# led_driver2.net
KiCad netlist of a schematic drawn in EAGLE
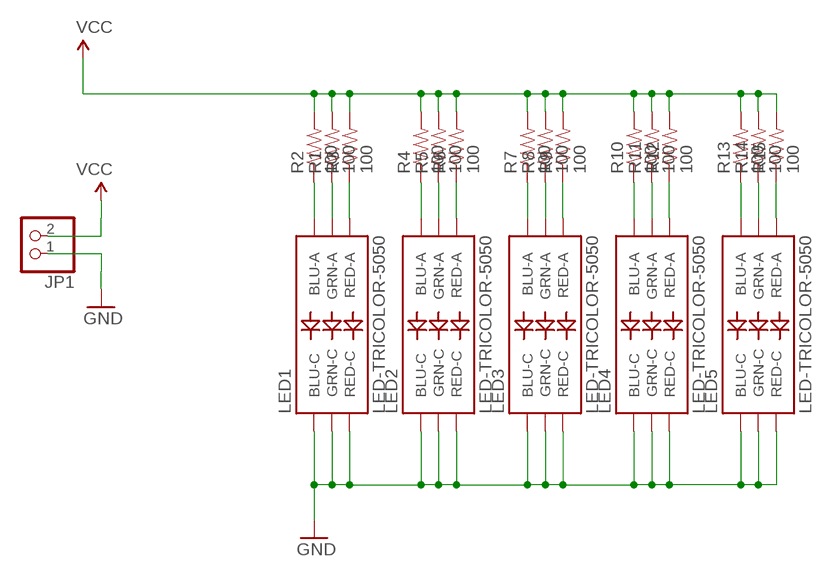
[diagram p0: schematic, sheet 1]

(export (version "E")
  (design (tool "Eeschema 10.0.6"))
  (components
    (comp (ref "JP1")
      (value "PINHD-1X2")
      (footprint "eagle-import:1X02")
      (libsource (lib "eagle-import") (part "PINHD-1X2"))
    )
    (comp (ref "LED1")
      (value "LED-TRICOLOR-5050")
      (footprint "eagle-import:LED-TRICOLOR-5050")
      (libsource (lib "eagle-import") (part "LED-TRICOLOR-5050"))
    )
    (comp (ref "LED2")
      (value "LED-TRICOLOR-5050")
      (footprint "eagle-import:LED-TRICOLOR-5050")
      (libsource (lib "eagle-import") (part "LED-TRICOLOR-5050"))
    )
    (comp (ref "LED3")
      (value "LED-TRICOLOR-5050")
      (footprint "eagle-import:LED-TRICOLOR-5050")
      (libsource (lib "eagle-import") (part "LED-TRICOLOR-5050"))
    )
    (comp (ref "LED4")
      (value "LED-TRICOLOR-5050")
      (footprint "eagle-import:LED-TRICOLOR-5050")
      (libsource (lib "eagle-import") (part "LED-TRICOLOR-5050"))
    )
    (comp (ref "LED5")
      (value "LED-TRICOLOR-5050")
      (footprint "eagle-import:LED-TRICOLOR-5050")
      (libsource (lib "eagle-import") (part "LED-TRICOLOR-5050"))
    )
    (comp (ref "R1")
      (value "100")
      (footprint "eagle-import:0603-RES")
      (libsource (lib "eagle-import") (part "RESISTOR0603-RES"))
    )
    (comp (ref "R2")
      (value "100")
      (footprint "eagle-import:0603-RES")
      (libsource (lib "eagle-import") (part "RESISTOR0603-RES"))
    )
    (comp (ref "R3")
      (value "100")
      (footprint "eagle-import:0603-RES")
      (libsource (lib "eagle-import") (part "RESISTOR0603-RES"))
    )
    (comp (ref "R4")
      (value "100")
      (footprint "eagle-import:0603-RES")
      (libsource (lib "eagle-import") (part "RESISTOR0603-RES"))
    )
    (comp (ref "R5")
      (value "100")
      (footprint "eagle-import:0603-RES")
      (libsource (lib "eagle-import") (part "RESISTOR0603-RES"))
    )
    (comp (ref "R6")
      (value "100")
      (footprint "eagle-import:0603-RES")
      (libsource (lib "eagle-import") (part "RESISTOR0603-RES"))
    )
    (comp (ref "R7")
      (value "100")
      (footprint "eagle-import:0603-RES")
      (libsource (lib "eagle-import") (part "RESISTOR0603-RES"))
    )
    (comp (ref "R8")
      (value "100")
      (footprint "eagle-import:0603-RES")
      (libsource (lib "eagle-import") (part "RESISTOR0603-RES"))
    )
    (comp (ref "R9")
      (value "100")
      (footprint "eagle-import:0603-RES")
      (libsource (lib "eagle-import") (part "RESISTOR0603-RES"))
    )
    (comp (ref "R10")
      (value "100")
      (footprint "eagle-import:0603-RES")
      (libsource (lib "eagle-import") (part "RESISTOR0603-RES"))
    )
    (comp (ref "R11")
      (value "100")
      (footprint "eagle-import:0603-RES")
      (libsource (lib "eagle-import") (part "RESISTOR0603-RES"))
    )
    (comp (ref "R12")
      (value "100")
      (footprint "eagle-import:0603-RES")
      (libsource (lib "eagle-import") (part "RESISTOR0603-RES"))
    )
    (comp (ref "R13")
      (value "100")
      (footprint "eagle-import:0603-RES")
      (libsource (lib "eagle-import") (part "RESISTOR0603-RES"))
    )
    (comp (ref "R14")
      (value "100")
      (footprint "eagle-import:0603-RES")
      (libsource (lib "eagle-import") (part "RESISTOR0603-RES"))
    )
    (comp (ref "R15")
      (value "100")
      (footprint "eagle-import:0603-RES")
      (libsource (lib "eagle-import") (part "RESISTOR0603-RES"))
    )
  )
  (nets
    (net (code "1") (name "GND") (class "Default")
      (node (ref "JP1") (pin "1") (pinfunction "1_1") (pintype "passive"))
      (node (ref "LED1") (pin "4") (pinfunction "BLU-C_4") (pintype "bidirectional"))
      (node (ref "LED1") (pin "5") (pinfunction "RED-C_5") (pintype "bidirectional"))
      (node (ref "LED1") (pin "6") (pinfunction "GRN-C_6") (pintype "bidirectional"))
      (node (ref "LED2") (pin "4") (pinfunction "BLU-C_4") (pintype "bidirectional"))
      (node (ref "LED2") (pin "5") (pinfunction "RED-C_5") (pintype "bidirectional"))
      (node (ref "LED2") (pin "6") (pinfunction "GRN-C_6") (pintype "bidirectional"))
      (node (ref "LED3") (pin "4") (pinfunction "BLU-C_4") (pintype "bidirectional"))
      (node (ref "LED3") (pin "5") (pinfunction "RED-C_5") (pintype "bidirectional"))
      (node (ref "LED3") (pin "6") (pinfunction "GRN-C_6") (pintype "bidirectional"))
      (node (ref "LED4") (pin "4") (pinfunction "BLU-C_4") (pintype "bidirectional"))
      (node (ref "LED4") (pin "5") (pinfunction "RED-C_5") (pintype "bidirectional"))
      (node (ref "LED4") (pin "6") (pinfunction "GRN-C_6") (pintype "bidirectional"))
      (node (ref "LED5") (pin "4") (pinfunction "BLU-C_4") (pintype "bidirectional"))
      (node (ref "LED5") (pin "5") (pinfunction "RED-C_5") (pintype "bidirectional"))
      (node (ref "LED5") (pin "6") (pinfunction "GRN-C_6") (pintype "bidirectional"))
    )
    (net (code "2") (name "Net-(LED1-BLU-A)") (class "Default")
      (node (ref "LED1") (pin "3") (pinfunction "BLU-A_3") (pintype "bidirectional"))
      (node (ref "R2") (pin "1") (pinfunction "1_1") (pintype "passive"))
    )
    (net (code "3") (name "Net-(LED1-GRN-A)") (class "Default")
      (node (ref "LED1") (pin "1") (pinfunction "GRN-A_1") (pintype "bidirectional"))
      (node (ref "R1") (pin "1") (pinfunction "1_1") (pintype "passive"))
    )
    (net (code "4") (name "Net-(LED1-RED-A)") (class "Default")
      (node (ref "LED1") (pin "2") (pinfunction "RED-A_2") (pintype "bidirectional"))
      (node (ref "R3") (pin "1") (pinfunction "1_1") (pintype "passive"))
    )
    (net (code "5") (name "Net-(LED2-BLU-A)") (class "Default")
      (node (ref "LED2") (pin "3") (pinfunction "BLU-A_3") (pintype "bidirectional"))
      (node (ref "R4") (pin "1") (pinfunction "1_1") (pintype "passive"))
    )
    (net (code "6") (name "Net-(LED2-GRN-A)") (class "Default")
      (node (ref "LED2") (pin "1") (pinfunction "GRN-A_1") (pintype "bidirectional"))
      (node (ref "R5") (pin "1") (pinfunction "1_1") (pintype "passive"))
    )
    (net (code "7") (name "Net-(LED2-RED-A)") (class "Default")
      (node (ref "LED2") (pin "2") (pinfunction "RED-A_2") (pintype "bidirectional"))
      (node (ref "R6") (pin "1") (pinfunction "1_1") (pintype "passive"))
    )
    (net (code "8") (name "Net-(LED3-BLU-A)") (class "Default")
      (node (ref "LED3") (pin "3") (pinfunction "BLU-A_3") (pintype "bidirectional"))
      (node (ref "R7") (pin "1") (pinfunction "1_1") (pintype "passive"))
    )
    (net (code "9") (name "Net-(LED3-GRN-A)") (class "Default")
      (node (ref "LED3") (pin "1") (pinfunction "GRN-A_1") (pintype "bidirectional"))
      (node (ref "R8") (pin "1") (pinfunction "1_1") (pintype "passive"))
    )
    (net (code "10") (name "Net-(LED3-RED-A)") (class "Default")
      (node (ref "LED3") (pin "2") (pinfunction "RED-A_2") (pintype "bidirectional"))
      (node (ref "R9") (pin "1") (pinfunction "1_1") (pintype "passive"))
    )
    (net (code "11") (name "Net-(LED4-BLU-A)") (class "Default")
      (node (ref "LED4") (pin "3") (pinfunction "BLU-A_3") (pintype "bidirectional"))
      (node (ref "R10") (pin "1") (pinfunction "1_1") (pintype "passive"))
    )
    (net (code "12") (name "Net-(LED4-GRN-A)") (class "Default")
      (node (ref "LED4") (pin "1") (pinfunction "GRN-A_1") (pintype "bidirectional"))
      (node (ref "R11") (pin "1") (pinfunction "1_1") (pintype "passive"))
    )
    (net (code "13") (name "Net-(LED4-RED-A)") (class "Default")
      (node (ref "LED4") (pin "2") (pinfunction "RED-A_2") (pintype "bidirectional"))
      (node (ref "R12") (pin "1") (pinfunction "1_1") (pintype "passive"))
    )
    (net (code "14") (name "Net-(LED5-BLU-A)") (class "Default")
      (node (ref "LED5") (pin "3") (pinfunction "BLU-A_3") (pintype "bidirectional"))
      (node (ref "R13") (pin "1") (pinfunction "1_1") (pintype "passive"))
    )
    (net (code "15") (name "Net-(LED5-GRN-A)") (class "Default")
      (node (ref "LED5") (pin "1") (pinfunction "GRN-A_1") (pintype "bidirectional"))
      (node (ref "R14") (pin "1") (pinfunction "1_1") (pintype "passive"))
    )
    (net (code "16") (name "Net-(LED5-RED-A)") (class "Default")
      (node (ref "LED5") (pin "2") (pinfunction "RED-A_2") (pintype "bidirectional"))
      (node (ref "R15") (pin "1") (pinfunction "1_1") (pintype "passive"))
    )
    (net (code "17") (name "VCC") (class "Default")
      (node (ref "JP1") (pin "2") (pinfunction "2_2") (pintype "passive"))
      (node (ref "R1") (pin "2") (pinfunction "2_2") (pintype "passive"))
      (node (ref "R10") (pin "2") (pinfunction "2_2") (pintype "passive"))
      (node (ref "R11") (pin "2") (pinfunction "2_2") (pintype "passive"))
      (node (ref "R12") (pin "2") (pinfunction "2_2") (pintype "passive"))
      (node (ref "R13") (pin "2") (pinfunction "2_2") (pintype "passive"))
      (node (ref "R14") (pin "2") (pinfunction "2_2") (pintype "passive"))
      (node (ref "R15") (pin "2") (pinfunction "2_2") (pintype "passive"))
      (node (ref "R2") (pin "2") (pinfunction "2_2") (pintype "passive"))
      (node (ref "R3") (pin "2") (pinfunction "2_2") (pintype "passive"))
      (node (ref "R4") (pin "2") (pinfunction "2_2") (pintype "passive"))
      (node (ref "R5") (pin "2") (pinfunction "2_2") (pintype "passive"))
      (node (ref "R6") (pin "2") (pinfunction "2_2") (pintype "passive"))
      (node (ref "R7") (pin "2") (pinfunction "2_2") (pintype "passive"))
      (node (ref "R8") (pin "2") (pinfunction "2_2") (pintype "passive"))
      (node (ref "R9") (pin "2") (pinfunction "2_2") (pintype "passive"))
    )
  )
)
